# Comms.net
KiCad netlist of a schematic drawn in Altium Designer
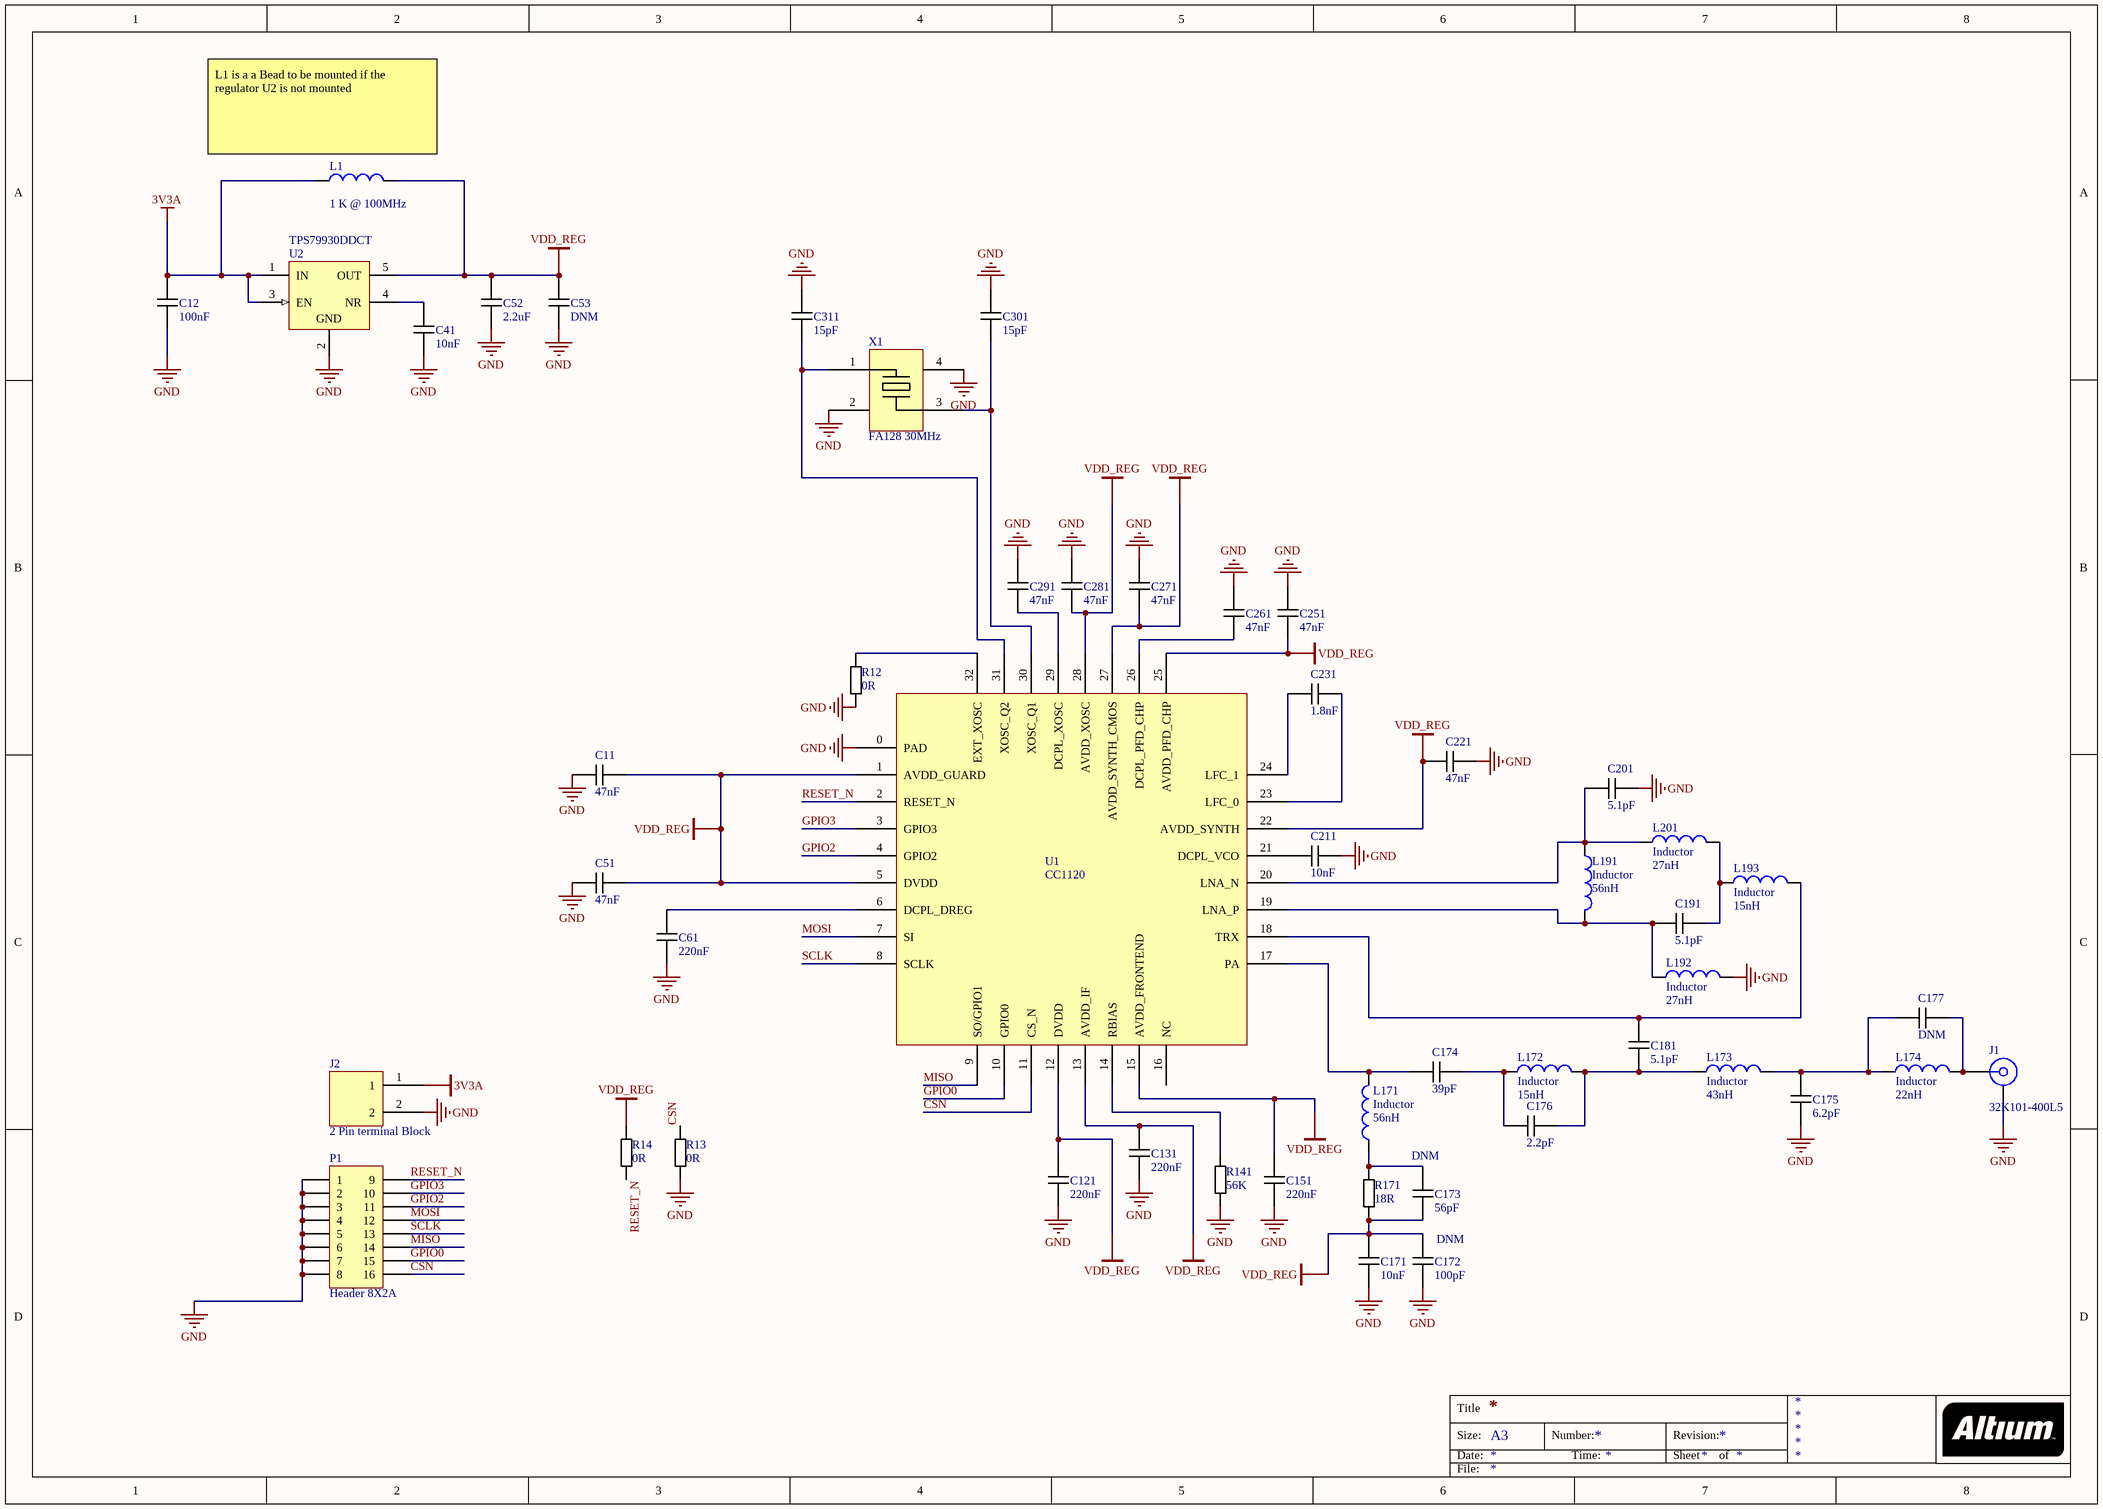
[diagram p0: Comms.SchDoc]

(export (version "E")
  (design (tool "Eeschema 10.0.6"))
  (components
    (comp (ref "C11")
      (value "47nF")
      (footprint "0805 Cap")
      (description "0805 MLCC - X7R, 10%")
      (fields (field (name "MANUFACTURER") "Kit") (field (name "Comment") "0805 Cap"))
      (libsource (lib "Tray 1 Expansion Board Prototype") (part "0805 MLCC - X7R, 10%"))
    )
    (comp (ref "C12")
      (value "100nF")
      (footprint "0805 Cap")
      (description "0805 MLCC - NP0, 5%")
      (fields (field (name "Comment") "0805 Cap"))
      (libsource (lib "Schlib1") (part "0805 MLCC - NP0, 5%"))
    )
    (comp (ref "C41")
      (value "10nF")
      (footprint "0805 Cap")
      (description "0805 MLCC - NP0, 5%")
      (fields (field (name "Comment") "0805 Cap"))
      (libsource (lib "Schlib1") (part "0805 MLCC - NP0, 5%"))
    )
    (comp (ref "C51")
      (value "47nF")
      (footprint "0805 Cap")
      (description "0805 MLCC - X7R, 10%")
      (fields (field (name "MANUFACTURER") "Kit") (field (name "Comment") "0805 Cap"))
      (libsource (lib "Tray 1 Expansion Board Prototype") (part "0805 MLCC - X7R, 10%"))
    )
    (comp (ref "C52")
      (value "2.2uF")
      (footprint "0805 Cap")
      (description "0805 MLCC - NP0, 5%")
      (fields (field (name "Comment") "0805 Cap"))
      (libsource (lib "Schlib1") (part "0805 MLCC - NP0, 5%"))
    )
    (comp (ref "C53")
      (value "DNM")
      (footprint "0805 Cap")
      (description "0805 MLCC - X7R, 10%")
      (fields (field (name "MANUFACTURER") "Kit"))
      (libsource (lib "Tray 1 Expansion Board Prototype") (part "0805 MLCC - X7R, 10%"))
    )
    (comp (ref "C61")
      (value "220nF")
      (footprint "0805 Cap")
      (description "0805 MLCC - X7R, 10%")
      (fields (field (name "MANUFACTURER") "Kit") (field (name "Comment") "0805 Cap"))
      (libsource (lib "Tray 1 Expansion Board Prototype") (part "0805 MLCC - X7R, 10%"))
    )
    (comp (ref "C121")
      (value "220nF")
      (footprint "0805 Cap")
      (description "0805 MLCC - X7R, 10%")
      (fields (field (name "MANUFACTURER") "Kit") (field (name "Comment") "0805 Cap"))
      (libsource (lib "Tray 1 Expansion Board Prototype") (part "0805 MLCC - X7R, 10%"))
    )
    (comp (ref "C131")
      (value "220nF")
      (footprint "0805 Cap")
      (description "0805 MLCC - X7R, 10%")
      (fields (field (name "MANUFACTURER") "Kit") (field (name "Comment") "0805 Cap"))
      (libsource (lib "Tray 1 Expansion Board Prototype") (part "0805 MLCC - X7R, 10%"))
    )
    (comp (ref "C151")
      (value "220nF")
      (footprint "0805 Cap")
      (description "0805 MLCC - X7R, 10%")
      (fields (field (name "MANUFACTURER") "Kit") (field (name "Comment") "0805 Cap"))
      (libsource (lib "Tray 1 Expansion Board Prototype") (part "0805 MLCC - X7R, 10%"))
    )
    (comp (ref "C171")
      (value "10nF")
      (footprint "0805 Cap")
      (description "0805 MLCC - NP0, 5%")
      (fields (field (name "Comment") "0805 Cap"))
      (libsource (lib "Schlib1") (part "0805 MLCC - NP0, 5%"))
    )
    (comp (ref "C172")
      (value "DNM")
      (footprint "0805 Cap")
      (description "0805 MLCC - NP0, 5%")
      (fields (field (name "ALTIUM_VALUE") "100pF"))
      (libsource (lib "Schlib1") (part "0805 MLCC - NP0, 5%"))
    )
    (comp (ref "C173")
      (value "DNM")
      (footprint "0805 Cap")
      (description "0805 MLCC - NP0, 5%")
      (fields (field (name "ALTIUM_VALUE") "56pF"))
      (libsource (lib "Schlib1") (part "0805 MLCC - NP0, 5%"))
    )
    (comp (ref "C174")
      (value "39pF")
      (footprint "0805 Cap")
      (description "0805 MLCC - NP0, 5%")
      (fields (field (name "Comment") "0805 Cap"))
      (libsource (lib "Schlib1") (part "0805 MLCC - NP0, 5%"))
    )
    (comp (ref "C175")
      (value "6.2pF")
      (footprint "0805 Cap")
      (description "0805 MLCC - NP0, 5%")
      (fields (field (name "Comment") "0805 Cap"))
      (libsource (lib "Schlib1") (part "0805 MLCC - NP0, 5%"))
    )
    (comp (ref "C176")
      (value "2.2pF")
      (footprint "0805 Cap")
      (description "0805 MLCC - NP0, 5%")
      (fields (field (name "Comment") "0805 Cap"))
      (libsource (lib "Schlib1") (part "0805 MLCC - NP0, 5%"))
    )
    (comp (ref "C177")
      (value "DNM")
      (footprint "0805 Cap")
      (description "0805 MLCC - X7R, 10%")
      (fields (field (name "MANUFACTURER") "Kit"))
      (libsource (lib "Tray 1 Expansion Board Prototype") (part "0805 MLCC - X7R, 10%"))
    )
    (comp (ref "C181")
      (value "5.1pF")
      (footprint "0805 Cap")
      (description "0805 MLCC - NP0, 5%")
      (fields (field (name "Comment") "0805 Cap"))
      (libsource (lib "Schlib1") (part "0805 MLCC - NP0, 5%"))
    )
    (comp (ref "C191")
      (value "5.1pF")
      (footprint "0805 Cap")
      (description "0805 MLCC - NP0, 5%")
      (fields (field (name "Comment") "0805 Cap"))
      (libsource (lib "Schlib1") (part "0805 MLCC - NP0, 5%"))
    )
    (comp (ref "C201")
      (value "5.1pF")
      (footprint "0805 Cap")
      (description "0805 MLCC - NP0, 5%")
      (fields (field (name "Comment") "0805 Cap"))
      (libsource (lib "Schlib1") (part "0805 MLCC - NP0, 5%"))
    )
    (comp (ref "C211")
      (value "10nF")
      (footprint "0805 Cap")
      (description "0805 MLCC - X7R, 10%")
      (fields (field (name "Comment") "0805 Cap"))
      (libsource (lib "Schlib1") (part "0805 MLCC - X7R, 10%"))
    )
    (comp (ref "C221")
      (value "47nF")
      (footprint "0805 Cap")
      (description "0805 MLCC - X7R, 10%")
      (fields (field (name "Comment") "0805 Cap"))
      (libsource (lib "Schlib1") (part "0805 MLCC - X7R, 10%"))
    )
    (comp (ref "C231")
      (value "1.8nF")
      (footprint "0805 Cap")
      (description "0805 MLCC - U2J, 5%")
      (fields (field (name "Comment") "0805 Cap"))
      (libsource (lib "Schlib1") (part "0805 MLCC - NP0, 5%"))
    )
    (comp (ref "C251")
      (value "47nF")
      (footprint "0805 Cap")
      (description "0805 MLCC - X7R, 10%")
      (fields (field (name "Comment") "0805 Cap"))
      (libsource (lib "Schlib1") (part "0805 MLCC - X7R, 10%"))
    )
    (comp (ref "C261")
      (value "47nF")
      (footprint "0805 Cap")
      (description "0805 MLCC - X7R, 10%")
      (fields (field (name "Comment") "0805 Cap"))
      (libsource (lib "Schlib1") (part "0805 MLCC - X7R, 10%"))
    )
    (comp (ref "C271")
      (value "47nF")
      (footprint "0805 Cap")
      (description "0805 MLCC - X7R, 10%")
      (fields (field (name "Comment") "0805 Cap"))
      (libsource (lib "Schlib1") (part "0805 MLCC - X7R, 10%"))
    )
    (comp (ref "C281")
      (value "47nF")
      (footprint "0805 Cap")
      (description "0805 MLCC - X7R, 10%")
      (fields (field (name "Comment") "0805 Cap"))
      (libsource (lib "Schlib1") (part "0805 MLCC - X7R, 10%"))
    )
    (comp (ref "C291")
      (value "47nF")
      (footprint "0805 Cap")
      (description "0805 MLCC - X7R, 10%")
      (fields (field (name "Comment") "0805 Cap"))
      (libsource (lib "Schlib1") (part "0805 MLCC - X7R, 10%"))
    )
    (comp (ref "C301")
      (value "15pF")
      (footprint "0805 Cap")
      (description "0805 MLCC - NP0, 5%")
      (fields (field (name "Comment") "0805 Cap"))
      (libsource (lib "Schlib1") (part "0805 MLCC - NP0, 5%"))
    )
    (comp (ref "C311")
      (value "15pF")
      (footprint "0805 Cap")
      (description "0805 MLCC - NP0, 5%")
      (fields (field (name "Comment") "0805 Cap"))
      (libsource (lib "Schlib1") (part "0805 MLCC - NP0, 5%"))
    )
    (comp (ref "J1")
      (value "32K101-400L5")
      (footprint "ROS-32K101-400L5_V")
      (description "SMA Straight Jack, Up to 18 GHz, -55 to 155 degC")
      (libsource (lib "Rosenberger SMA") (part "32K101-400L5"))
    )
    (comp (ref "J2")
      (value "2 Pin terminal Block")
      (footprint "5.05mm Terminal Block - 2")
      (libsource (lib "Schlib1") (part "2 Terminal Block"))
    )
    (comp (ref "L1")
      (value "1 K @ 100MHz")
      (description "digikey: 490-1041-1-ND")
      (fields (field (name "PUBLISHER") "Altium Limited"))
      (libsource (lib "Miscellaneous Devices") (part "Inductor"))
    )
    (comp (ref "L171")
      (value "Inductor")
      (fields (field (name "ALTIUM_VALUE") "56nH") (field (name "PUBLISHER") "Altium Limited"))
      (libsource (lib "Miscellaneous Devices") (part "Inductor"))
    )
    (comp (ref "L172")
      (value "Inductor")
      (fields (field (name "ALTIUM_VALUE") "15nH") (field (name "PUBLISHER") "Altium Limited"))
      (libsource (lib "Miscellaneous Devices") (part "Inductor"))
    )
    (comp (ref "L173")
      (value "Inductor")
      (fields (field (name "ALTIUM_VALUE") "43nH") (field (name "PUBLISHER") "Altium Limited"))
      (libsource (lib "Miscellaneous Devices") (part "Inductor"))
    )
    (comp (ref "L174")
      (value "Inductor")
      (fields (field (name "ALTIUM_VALUE") "22nH") (field (name "PUBLISHER") "Altium Limited"))
      (libsource (lib "Miscellaneous Devices") (part "Inductor"))
    )
    (comp (ref "L191")
      (value "Inductor")
      (footprint "0805 Resistor")
      (fields (field (name "ALTIUM_VALUE") "56nH") (field (name "PUBLISHER") "Altium Limited"))
      (libsource (lib "Miscellaneous Devices") (part "Inductor"))
    )
    (comp (ref "L192")
      (value "Inductor")
      (footprint "0805 Resistor")
      (fields (field (name "ALTIUM_VALUE") "27nH") (field (name "PUBLISHER") "Altium Limited"))
      (libsource (lib "Miscellaneous Devices") (part "Inductor"))
    )
    (comp (ref "L193")
      (value "Inductor")
      (fields (field (name "ALTIUM_VALUE") "15nH") (field (name "PUBLISHER") "Altium Limited"))
      (libsource (lib "Miscellaneous Devices") (part "Inductor"))
    )
    (comp (ref "L201")
      (value "Inductor")
      (footprint "0805 Resistor")
      (fields (field (name "ALTIUM_VALUE") "27nH") (field (name "PUBLISHER") "Altium Limited"))
      (libsource (lib "Miscellaneous Devices") (part "Inductor"))
    )
    (comp (ref "P1")
      (value "Header 8X2A")
      (footprint "HDR2X8_CEN")
      (description "Header, 8-Pin, Dual row")
      (fields (field (name "PUBLISHER") "Altium Limited"))
      (libsource (lib "Miscellaneous Connectors") (part "Header 8X2A"))
    )
    (comp (ref "R12")
      (value "0R")
      (footprint "0805 Resistor")
      (description "0805 Thick Film Resistor 1%")
      (fields (field (name "Comment") "0805 Resistor"))
      (libsource (lib "Schlib1") (part "0805 Thick Film Resistor 1%"))
    )
    (comp (ref "R13")
      (value "0R")
      (footprint "0805 Resistor")
      (description "0805 Thick Film Resistor 1%")
      (fields (field (name "Comment") "0805 Resistor"))
      (libsource (lib "Schlib1") (part "0805 Thick Film Resistor 1%"))
    )
    (comp (ref "R14")
      (value "0R")
      (footprint "0805 Resistor")
      (description "0805 Thick Film Resistor 1%")
      (fields (field (name "Comment") "0805 Resistor"))
      (libsource (lib "") (part "0805 Thick Film Resistor 1%_1"))
    )
    (comp (ref "R141")
      (value "56K")
      (footprint "0805 Resistor")
      (description "0805 Thick Film Resistor 1%")
      (fields (field (name "MANUFACTURER") "Stackpole Electronics") (field (name "Comment") "0805 Resistor"))
      (libsource (lib "Tray 1 Expansion Board Prototype") (part "0805 Thick Film Resistor 1%"))
    )
    (comp (ref "R171")
      (value "18R")
      (footprint "0805 Resistor")
      (description "0805 Thick Film Resistor 1%")
      (fields (field (name "Comment") "0805 Resistor"))
      (libsource (lib "Schlib1") (part "0805 Thick Film Resistor 1%"))
    )
    (comp (ref "U1")
      (value "CC1120")
      (footprint "TI-RHB")
      (description "Digi-Key Part Number 296-35667-1-ND")
      (libsource (lib "Comms") (part "CC1120"))
    )
    (comp (ref "U2")
      (value "TPS79930DDCT")
      (footprint "TI-DDC5_N")
      (fields (field (name "MANUFACTURER") "Texas Instruments"))
      (libsource (lib "TI Power Management Linear Regulator Single Channel LDO (0-350mA)") (part "TPS79930DDCT"))
    )
    (comp (ref "X1")
      (value "FA128 30MHz")
      (footprint "FA128")
      (libsource (lib "Integrated_circuits") (part "4-Pin Oscillator"))
    )
  )
  (nets
    (net (code "1") (name "/CSN") (class "Default")
      (node (ref "P1") (pin "16") (pinfunction "16_16") (pintype "passive"))
      (node (ref "R13") (pin "2") (pinfunction "2_2") (pintype "passive"))
      (node (ref "U1") (pin "11") (pinfunction "CS_N_11") (pintype "passive"))
    )
    (net (code "2") (name "/GPIO0") (class "Default")
      (node (ref "P1") (pin "15") (pinfunction "15_15") (pintype "passive"))
      (node (ref "U1") (pin "10") (pinfunction "GPIO0_10") (pintype "passive"))
    )
    (net (code "3") (name "/GPIO2") (class "Default")
      (node (ref "P1") (pin "11") (pinfunction "11_11") (pintype "passive"))
      (node (ref "U1") (pin "4") (pinfunction "GPIO2_4") (pintype "passive"))
    )
    (net (code "4") (name "/GPIO3") (class "Default")
      (node (ref "P1") (pin "10") (pinfunction "10_10") (pintype "passive"))
      (node (ref "U1") (pin "3") (pinfunction "GPIO3_3") (pintype "passive"))
    )
    (net (code "5") (name "/MISO") (class "Default")
      (node (ref "P1") (pin "14") (pinfunction "14_14") (pintype "passive"))
      (node (ref "U1") (pin "9") (pinfunction "SO/GPIO1_9") (pintype "passive"))
    )
    (net (code "6") (name "/MOSI") (class "Default")
      (node (ref "P1") (pin "12") (pinfunction "12_12") (pintype "passive"))
      (node (ref "U1") (pin "7") (pinfunction "SI_7") (pintype "passive"))
    )
    (net (code "7") (name "/RESET_N") (class "Default")
      (node (ref "P1") (pin "9") (pinfunction "9_9") (pintype "passive"))
      (node (ref "R14") (pin "2") (pinfunction "2_2") (pintype "passive"))
      (node (ref "U1") (pin "2") (pinfunction "RESET_N_2") (pintype "passive"))
    )
    (net (code "8") (name "/SCLK") (class "Default")
      (node (ref "P1") (pin "13") (pinfunction "13_13") (pintype "passive"))
      (node (ref "U1") (pin "8") (pinfunction "SCLK_8") (pintype "passive"))
    )
    (net (code "9") (name "3V3A") (class "Default")
      (node (ref "C12") (pin "2") (pinfunction "2_2") (pintype "passive"))
      (node (ref "J2") (pin "1") (pinfunction "1_1") (pintype "passive"))
      (node (ref "L1") (pin "1") (pinfunction "1_1") (pintype "passive"))
      (node (ref "U2") (pin "1") (pinfunction "IN_1") (pintype "power_in"))
      (node (ref "U2") (pin "3") (pinfunction "EN_3") (pintype "input"))
    )
    (net (code "10") (name "GND") (class "Default")
      (node (ref "C11") (pin "2") (pinfunction "2_2") (pintype "passive"))
      (node (ref "C12") (pin "1") (pinfunction "1_1") (pintype "passive"))
      (node (ref "C121") (pin "1") (pinfunction "1_1") (pintype "passive"))
      (node (ref "C131") (pin "1") (pinfunction "1_1") (pintype "passive"))
      (node (ref "C151") (pin "1") (pinfunction "1_1") (pintype "passive"))
      (node (ref "C171") (pin "1") (pinfunction "1_1") (pintype "passive"))
      (node (ref "C172") (pin "1") (pinfunction "1_1") (pintype "passive"))
      (node (ref "C175") (pin "2") (pinfunction "2_2") (pintype "passive"))
      (node (ref "C201") (pin "2") (pinfunction "2_2") (pintype "passive"))
      (node (ref "C211") (pin "2") (pinfunction "2_2") (pintype "passive"))
      (node (ref "C221") (pin "2") (pinfunction "2_2") (pintype "passive"))
      (node (ref "C251") (pin "2") (pinfunction "2_2") (pintype "passive"))
      (node (ref "C261") (pin "2") (pinfunction "2_2") (pintype "passive"))
      (node (ref "C271") (pin "2") (pinfunction "2_2") (pintype "passive"))
      (node (ref "C281") (pin "2") (pinfunction "2_2") (pintype "passive"))
      (node (ref "C291") (pin "2") (pinfunction "2_2") (pintype "passive"))
      (node (ref "C301") (pin "2") (pinfunction "2_2") (pintype "passive"))
      (node (ref "C311") (pin "2") (pinfunction "2_2") (pintype "passive"))
      (node (ref "C41") (pin "1") (pinfunction "1_1") (pintype "passive"))
      (node (ref "C51") (pin "2") (pinfunction "2_2") (pintype "passive"))
      (node (ref "C52") (pin "1") (pinfunction "1_1") (pintype "passive"))
      (node (ref "C53") (pin "2") (pinfunction "2_2") (pintype "passive"))
      (node (ref "C61") (pin "2") (pinfunction "2_2") (pintype "passive"))
      (node (ref "J1") (pin "MH") (pinfunction "MH_MH") (pintype "passive"))
      (node (ref "J2") (pin "2") (pinfunction "2_2") (pintype "passive"))
      (node (ref "L192") (pin "2") (pinfunction "2_2") (pintype "passive"))
      (node (ref "P1") (pin "1") (pinfunction "1_1") (pintype "passive"))
      (node (ref "P1") (pin "2") (pinfunction "2_2") (pintype "passive"))
      (node (ref "P1") (pin "3") (pinfunction "3_3") (pintype "passive"))
      (node (ref "P1") (pin "4") (pinfunction "4_4") (pintype "passive"))
      (node (ref "P1") (pin "5") (pinfunction "5_5") (pintype "passive"))
      (node (ref "P1") (pin "6") (pinfunction "6_6") (pintype "passive"))
      (node (ref "P1") (pin "7") (pinfunction "7_7") (pintype "passive"))
      (node (ref "P1") (pin "8") (pinfunction "8_8") (pintype "passive"))
      (node (ref "R12") (pin "1") (pinfunction "1_1") (pintype "passive"))
      (node (ref "R13") (pin "1") (pinfunction "1_1") (pintype "passive"))
      (node (ref "R141") (pin "2") (pinfunction "2_2") (pintype "passive"))
      (node (ref "U1") (pin "0") (pinfunction "PAD_0") (pintype "passive"))
      (node (ref "U2") (pin "2") (pinfunction "GND_2") (pintype "power_in"))
      (node (ref "X1") (pin "2") (pinfunction "2_2") (pintype "passive"))
      (node (ref "X1") (pin "4") (pinfunction "4_4") (pintype "passive"))
    )
    (net (code "11") (name "Net-(C173-Pad2)") (class "Default")
      (node (ref "C173") (pin "2") (pinfunction "2_2") (pintype "passive"))
      (node (ref "L171") (pin "1") (pinfunction "1_1") (pintype "passive"))
      (node (ref "R171") (pin "2") (pinfunction "2_2") (pintype "passive"))
    )
    (net (code "12") (name "Net-(C174-Pad1)") (class "Default")
      (node (ref "C174") (pin "1") (pinfunction "1_1") (pintype "passive"))
      (node (ref "C176") (pin "1") (pinfunction "1_1") (pintype "passive"))
      (node (ref "L172") (pin "1") (pinfunction "1_1") (pintype "passive"))
    )
    (net (code "13") (name "Net-(C175-Pad1)") (class "Default")
      (node (ref "C175") (pin "1") (pinfunction "1_1") (pintype "passive"))
      (node (ref "C177") (pin "2") (pinfunction "2_2") (pintype "passive"))
      (node (ref "L173") (pin "2") (pinfunction "2_2") (pintype "passive"))
      (node (ref "L174") (pin "1") (pinfunction "1_1") (pintype "passive"))
    )
    (net (code "14") (name "Net-(C176-Pad2)") (class "Default")
      (node (ref "C176") (pin "2") (pinfunction "2_2") (pintype "passive"))
      (node (ref "C181") (pin "1") (pinfunction "1_1") (pintype "passive"))
      (node (ref "L172") (pin "2") (pinfunction "2_2") (pintype "passive"))
      (node (ref "L173") (pin "1") (pinfunction "1_1") (pintype "passive"))
    )
    (net (code "15") (name "Net-(C177-Pad1)") (class "Default")
      (node (ref "C177") (pin "1") (pinfunction "1_1") (pintype "passive"))
      (node (ref "J1") (pin "1") (pinfunction "1_1") (pintype "passive"))
      (node (ref "L174") (pin "2") (pinfunction "2_2") (pintype "passive"))
    )
    (net (code "16") (name "Net-(C191-Pad2)") (class "Default")
      (node (ref "C191") (pin "2") (pinfunction "2_2") (pintype "passive"))
      (node (ref "L193") (pin "1") (pinfunction "1_1") (pintype "passive"))
      (node (ref "L201") (pin "2") (pinfunction "2_2") (pintype "passive"))
    )
    (net (code "17") (name "Net-(U1-DCPL_DREG)") (class "Default")
      (node (ref "C61") (pin "1") (pinfunction "1_1") (pintype "passive"))
      (node (ref "U1") (pin "6") (pinfunction "DCPL_DREG_6") (pintype "passive"))
    )
    (net (code "18") (name "Net-(U1-DCPL_PFD_CHP)") (class "Default")
      (node (ref "C261") (pin "1") (pinfunction "1_1") (pintype "passive"))
      (node (ref "U1") (pin "26") (pinfunction "DCPL_PFD_CHP_26") (pintype "passive"))
    )
    (net (code "19") (name "Net-(U1-DCPL_VCO)") (class "Default")
      (node (ref "C211") (pin "1") (pinfunction "1_1") (pintype "passive"))
      (node (ref "U1") (pin "21") (pinfunction "DCPL_VCO_21") (pintype "passive"))
    )
    (net (code "20") (name "Net-(U1-DCPL_XOSC)") (class "Default")
      (node (ref "C291") (pin "1") (pinfunction "1_1") (pintype "passive"))
      (node (ref "U1") (pin "29") (pinfunction "DCPL_XOSC_29") (pintype "passive"))
    )
    (net (code "21") (name "Net-(U1-EXT_XOSC)") (class "Default")
      (node (ref "R12") (pin "2") (pinfunction "2_2") (pintype "passive"))
      (node (ref "U1") (pin "32") (pinfunction "EXT_XOSC_32") (pintype "passive"))
    )
    (net (code "22") (name "Net-(U1-LFC_0)") (class "Default")
      (node (ref "C231") (pin "2") (pinfunction "2_2") (pintype "passive"))
      (node (ref "U1") (pin "23") (pinfunction "LFC_0_23") (pintype "passive"))
    )
    (net (code "23") (name "Net-(U1-LFC_1)") (class "Default")
      (node (ref "C231") (pin "1") (pinfunction "1_1") (pintype "passive"))
      (node (ref "U1") (pin "24") (pinfunction "LFC_1_24") (pintype "passive"))
    )
    (net (code "24") (name "Net-(U1-LNA_N)") (class "Default")
      (node (ref "C201") (pin "1") (pinfunction "1_1") (pintype "passive"))
      (node (ref "L191") (pin "1") (pinfunction "1_1") (pintype "passive"))
      (node (ref "L201") (pin "1") (pinfunction "1_1") (pintype "passive"))
      (node (ref "U1") (pin "20") (pinfunction "LNA_N_20") (pintype "passive"))
    )
    (net (code "25") (name "Net-(U1-LNA_P)") (class "Default")
      (node (ref "C191") (pin "1") (pinfunction "1_1") (pintype "passive"))
      (node (ref "L191") (pin "2") (pinfunction "2_2") (pintype "passive"))
      (node (ref "L192") (pin "1") (pinfunction "1_1") (pintype "passive"))
      (node (ref "U1") (pin "19") (pinfunction "LNA_P_19") (pintype "passive"))
    )
    (net (code "26") (name "Net-(U1-PA)") (class "Default")
      (node (ref "C174") (pin "2") (pinfunction "2_2") (pintype "passive"))
      (node (ref "L171") (pin "2") (pinfunction "2_2") (pintype "passive"))
      (node (ref "U1") (pin "17") (pinfunction "PA_17") (pintype "passive"))
    )
    (net (code "27") (name "Net-(U1-RBIAS)") (class "Default")
      (node (ref "R141") (pin "1") (pinfunction "1_1") (pintype "passive"))
      (node (ref "U1") (pin "14") (pinfunction "RBIAS_14") (pintype "passive"))
    )
    (net (code "28") (name "Net-(U1-TRX)") (class "Default")
      (node (ref "C181") (pin "2") (pinfunction "2_2") (pintype "passive"))
      (node (ref "L193") (pin "2") (pinfunction "2_2") (pintype "passive"))
      (node (ref "U1") (pin "18") (pinfunction "TRX_18") (pintype "passive"))
    )
    (net (code "29") (name "Net-(U1-XOSC_Q1)") (class "Default")
      (node (ref "C301") (pin "1") (pinfunction "1_1") (pintype "passive"))
      (node (ref "U1") (pin "30") (pinfunction "XOSC_Q1_30") (pintype "passive"))
      (node (ref "X1") (pin "3") (pinfunction "3_3") (pintype "passive"))
    )
    (net (code "30") (name "Net-(U1-XOSC_Q2)") (class "Default")
      (node (ref "C311") (pin "1") (pinfunction "1_1") (pintype "passive"))
      (node (ref "U1") (pin "31") (pinfunction "XOSC_Q2_31") (pintype "passive"))
      (node (ref "X1") (pin "1") (pinfunction "1_1") (pintype "passive"))
    )
    (net (code "31") (name "Net-(U2-NR)") (class "Default")
      (node (ref "C41") (pin "2") (pinfunction "2_2") (pintype "passive"))
      (node (ref "U2") (pin "4") (pinfunction "NR_4") (pintype "passive"))
    )
    (net (code "32") (name "VDD_REG") (class "Default")
      (node (ref "C11") (pin "1") (pinfunction "1_1") (pintype "passive"))
      (node (ref "C121") (pin "2") (pinfunction "2_2") (pintype "passive"))
      (node (ref "C131") (pin "2") (pinfunction "2_2") (pintype "passive"))
      (node (ref "C151") (pin "2") (pinfunction "2_2") (pintype "passive"))
      (node (ref "C171") (pin "2") (pinfunction "2_2") (pintype "passive"))
      (node (ref "C172") (pin "2") (pinfunction "2_2") (pintype "passive"))
      (node (ref "C173") (pin "1") (pinfunction "1_1") (pintype "passive"))
      (node (ref "C221") (pin "1") (pinfunction "1_1") (pintype "passive"))
      (node (ref "C251") (pin "1") (pinfunction "1_1") (pintype "passive"))
      (node (ref "C271") (pin "1") (pinfunction "1_1") (pintype "passive"))
      (node (ref "C281") (pin "1") (pinfunction "1_1") (pintype "passive"))
      (node (ref "C51") (pin "1") (pinfunction "1_1") (pintype "passive"))
      (node (ref "C52") (pin "2") (pinfunction "2_2") (pintype "passive"))
      (node (ref "C53") (pin "1") (pinfunction "1_1") (pintype "passive"))
      (node (ref "L1") (pin "2") (pinfunction "2_2") (pintype "passive"))
      (node (ref "R14") (pin "1") (pinfunction "1_1") (pintype "passive"))
      (node (ref "R171") (pin "1") (pinfunction "1_1") (pintype "passive"))
      (node (ref "U1") (pin "1") (pinfunction "AVDD_GUARD_1") (pintype "passive"))
      (node (ref "U1") (pin "12") (pinfunction "DVDD_12") (pintype "passive"))
      (node (ref "U1") (pin "13") (pinfunction "AVDD_IF_13") (pintype "passive"))
      (node (ref "U1") (pin "15") (pinfunction "AVDD_FRONTEND_15") (pintype "passive"))
      (node (ref "U1") (pin "22") (pinfunction "AVDD_SYNTH_22") (pintype "passive"))
      (node (ref "U1") (pin "25") (pinfunction "AVDD_PFD_CHP_25") (pintype "passive"))
      (node (ref "U1") (pin "27") (pinfunction "AVDD_SYNTH_CMOS_27") (pintype "passive"))
      (node (ref "U1") (pin "28") (pinfunction "AVDD_XOSC_28") (pintype "passive"))
      (node (ref "U1") (pin "5") (pinfunction "DVDD_5") (pintype "passive"))
      (node (ref "U2") (pin "5") (pinfunction "OUT_5") (pintype "power_in"))
    )
    (net (code "33") (name "unconnected-(U1-NC-Pad16)") (class "Default")
      (node (ref "U1") (pin "16") (pinfunction "NC_16") (pintype "passive"))
    )
  )
)
